# Buck.net
KiCad netlist of a schematic drawn in Altium Designer
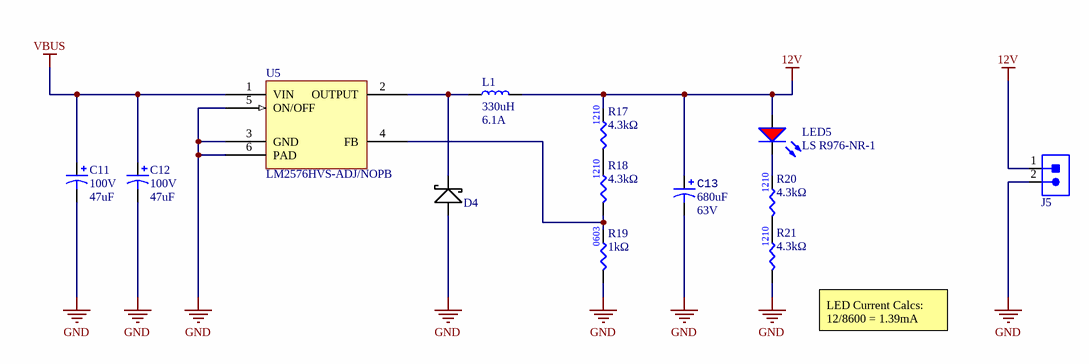
[diagram p0: Buck.SchDoc]

(export (version "E")
  (design (tool "Eeschema 10.0.6"))
  (components
    (comp (ref "C11")
      (value "CAP_47uF_100V_ALUM")
      (footprint "RADIAL_CORNELL_D")
      (fields
        (field (name "MANUFACTURER") "Nichicon")
        (field (name "MANUFACTURER PART NUMBER") "UCD2A470MNQ1MS")
        (field (name "VOLTAGE RATING") "100V")
        (field (name "CAPACITANCE") "47uF")
      )
      (libsource (lib "UWRT_Schematic_Library_2020") (part "CAP_47uF_100V_ALUM"))
    )
    (comp (ref "C12")
      (value "CAP_47uF_100V_ALUM")
      (footprint "RADIAL_CORNELL_D")
      (fields
        (field (name "MANUFACTURER") "Nichicon")
        (field (name "MANUFACTURER PART NUMBER") "UCD2A470MNQ1MS")
        (field (name "VOLTAGE RATING") "100V")
        (field (name "CAPACITANCE") "47uF")
      )
      (libsource (lib "UWRT_Schematic_Library_2020") (part "CAP_47uF_100V_ALUM"))
    )
    (comp (ref "C13")
      (value "680uF")
      (footprint "ELXZ630ELL681MM20S")
      (description "CAP ALUM 680UF 20% 63V RADIAL")
      (fields
        (field (name "VOLTAGE") "63V")
        (field (name "VOLTAGE RATING") "63V")
        (field (name "Comment") "CAP_680uF_63V_ALUM")
      )
      (libsource (lib "UWRT_Schematic_Library_2020") (part "CAP_680uF_63V_ALUM"))
    )
    (comp (ref "D4")
      (value "DIO_SCHOTTKY_20V_3A")
      (footprint "SS32")
      (description "DIODE SCHOTTKY 20V 3A SMC")
      (fields (field (name "PART NUMBER") "SS32"))
      (libsource (lib "UWRT_Schematic_Library_2020") (part "DIO_SCHOTTKY_20V_3A"))
    )
    (comp (ref "J5")
      (value "CON_2POS_SCREW_TERM")
      (footprint "1935161")
      (description "TERM BLK 2POS SIDE ENTRY 5MM")
      (libsource (lib "UWRT_Schematic_Library_2020") (part "CON_2POS_SCREW_TERM"))
    )
    (comp (ref "L1")
      (value "IND_330uH_6.1A")
      (footprint "74437529203331")
      (description "General Purpose Inductor")
      (fields
        (field (name "MANUFACTURER") "Wurth Electronics")
        (field (name "MANUFACTURER PART NUMBER") "74437529203331")
        (field (name "CURRENT RATING") "6.1A")
        (field (name "INDUCTANCE") "330uH")
      )
      (libsource (lib "UWRT_Schematic_Library_2020") (part "IND_330uH_6.1A"))
    )
    (comp (ref "LED5")
      (value "LED_RED")
      (footprint "LED_0805_RED")
      (description "LED RED DIFFUSED 0805 SMD")
      (fields (field (name "MANUFACTURER PART NUMBER 1") "LS R976-NR-1"))
      (libsource (lib "UWRT_Schematic_Library_2020") (part "LED_RED"))
    )
    (comp (ref "R17")
      (value "4.3kΩ")
      (footprint "RES1210")
      (description "RES 4.3K OHM 5% 1/2W 1210")
      (fields (field (name "TOLERANCE") "5%") (field (name "Comment") "RES_4.3kΩ_1210_5%"))
      (libsource (lib "UWRT_Schematic_Library_2020") (part "RES_4.3kΩ_1210_5%"))
    )
    (comp (ref "R18")
      (value "4.3kΩ")
      (footprint "RES1210")
      (description "RES 4.3K OHM 5% 1/2W 1210")
      (fields (field (name "TOLERANCE") "5%") (field (name "Comment") "RES_4.3kΩ_1210_5%"))
      (libsource (lib "UWRT_Schematic_Library_2020") (part "RES_4.3kΩ_1210_5%"))
    )
    (comp (ref "R19")
      (value "1kΩ")
      (footprint "RES0603")
      (description "RES 1K OHM 5% 1/10W 0603")
      (fields (field (name "Comment") "RES_1kΩ_0603_5%"))
      (libsource (lib "UWRT_Schematic_Library_2020") (part "RES_1kΩ_0603_5%"))
    )
    (comp (ref "R20")
      (value "4.3kΩ")
      (footprint "RES1210")
      (description "RES 4.3K OHM 5% 1/2W 1210")
      (fields (field (name "TOLERANCE") "5%") (field (name "Comment") "RES_4.3kΩ_1210_5%"))
      (libsource (lib "UWRT_Schematic_Library_2020") (part "RES_4.3kΩ_1210_5%"))
    )
    (comp (ref "R21")
      (value "4.3kΩ")
      (footprint "RES1210")
      (description "RES 4.3K OHM 5% 1/2W 1210")
      (fields (field (name "TOLERANCE") "5%") (field (name "Comment") "RES_4.3kΩ_1210_5%"))
      (libsource (lib "UWRT_Schematic_Library_2020") (part "RES_4.3kΩ_1210_5%"))
    )
    (comp (ref "U5")
      (value "BUCK_ADJ_4_57_V")
      (footprint "D2PAK-5")
      (description "Switching Regulator, Voltage-mode, 7.5A, 63kHz Switching Freq-Max, BIPolar, PSSO5")
      (fields
        (field (name "MANUFACTURER") "TI National Semiconductor")
        (field (name "MANUFACTURER PART NUMBER") "LM2576HVS-ADJ/NOPB")
      )
      (libsource (lib "UWRT_Schematic_Library_2020") (part "BUCK_ADJ_4_57_V"))
    )
  )
  (nets
    (net (code "1") (name "12V") (class "Default")
      (node (ref "C13") (pin "1") (pinfunction "1_1") (pintype "passive"))
      (node (ref "J5") (pin "1") (pinfunction "1_1") (pintype "passive"))
      (node (ref "L1") (pin "2") (pinfunction "2_2") (pintype "passive"))
      (node (ref "LED5") (pin "1") (pinfunction "A_1") (pintype "passive"))
      (node (ref "R17") (pin "2") (pinfunction "2_2") (pintype "passive"))
    )
    (net (code "2") (name "GND") (class "Default")
      (node (ref "C11") (pin "2") (pinfunction "2_2") (pintype "passive"))
      (node (ref "C12") (pin "2") (pinfunction "2_2") (pintype "passive"))
      (node (ref "C13") (pin "2") (pinfunction "2_2") (pintype "passive"))
      (node (ref "D4") (pin "2") (pinfunction "A_2") (pintype "passive"))
      (node (ref "J5") (pin "2") (pinfunction "2_2") (pintype "passive"))
      (node (ref "R19") (pin "1") (pinfunction "1_1") (pintype "passive"))
      (node (ref "R21") (pin "1") (pinfunction "1_1") (pintype "passive"))
      (node (ref "U5") (pin "3") (pinfunction "GND_3") (pintype "power_in"))
      (node (ref "U5") (pin "5") (pinfunction "ON/OFF_5") (pintype "input"))
      (node (ref "U5") (pin "6") (pinfunction "PAD_6") (pintype "power_in"))
    )
    (net (code "3") (name "Net-(D4-K)") (class "Default")
      (node (ref "D4") (pin "1") (pinfunction "K_1") (pintype "passive"))
      (node (ref "L1") (pin "1") (pinfunction "1_1") (pintype "passive"))
      (node (ref "U5") (pin "2") (pinfunction "OUTPUT_2") (pintype "power_in"))
    )
    (net (code "4") (name "Net-(LED5-K)") (class "Default")
      (node (ref "LED5") (pin "2") (pinfunction "K_2") (pintype "passive"))
      (node (ref "R20") (pin "2") (pinfunction "2_2") (pintype "passive"))
    )
    (net (code "5") (name "Net-(R17-Pad1)") (class "Default")
      (node (ref "R17") (pin "1") (pinfunction "1_1") (pintype "passive"))
      (node (ref "R18") (pin "2") (pinfunction "2_2") (pintype "passive"))
    )
    (net (code "6") (name "Net-(R20-Pad1)") (class "Default")
      (node (ref "R20") (pin "1") (pinfunction "1_1") (pintype "passive"))
      (node (ref "R21") (pin "2") (pinfunction "2_2") (pintype "passive"))
    )
    (net (code "7") (name "Net-(U5-FB)") (class "Default")
      (node (ref "R18") (pin "1") (pinfunction "1_1") (pintype "passive"))
      (node (ref "R19") (pin "2") (pinfunction "2_2") (pintype "passive"))
      (node (ref "U5") (pin "4") (pinfunction "FB_4") (pintype "passive"))
    )
    (net (code "8") (name "VBUS") (class "Default")
      (node (ref "C11") (pin "1") (pinfunction "1_1") (pintype "passive"))
      (node (ref "C12") (pin "1") (pinfunction "1_1") (pintype "passive"))
      (node (ref "U5") (pin "1") (pinfunction "VIN_1") (pintype "power_in"))
    )
  )
)
